# HD.net
KiCad netlist of a schematic drawn in EAGLE
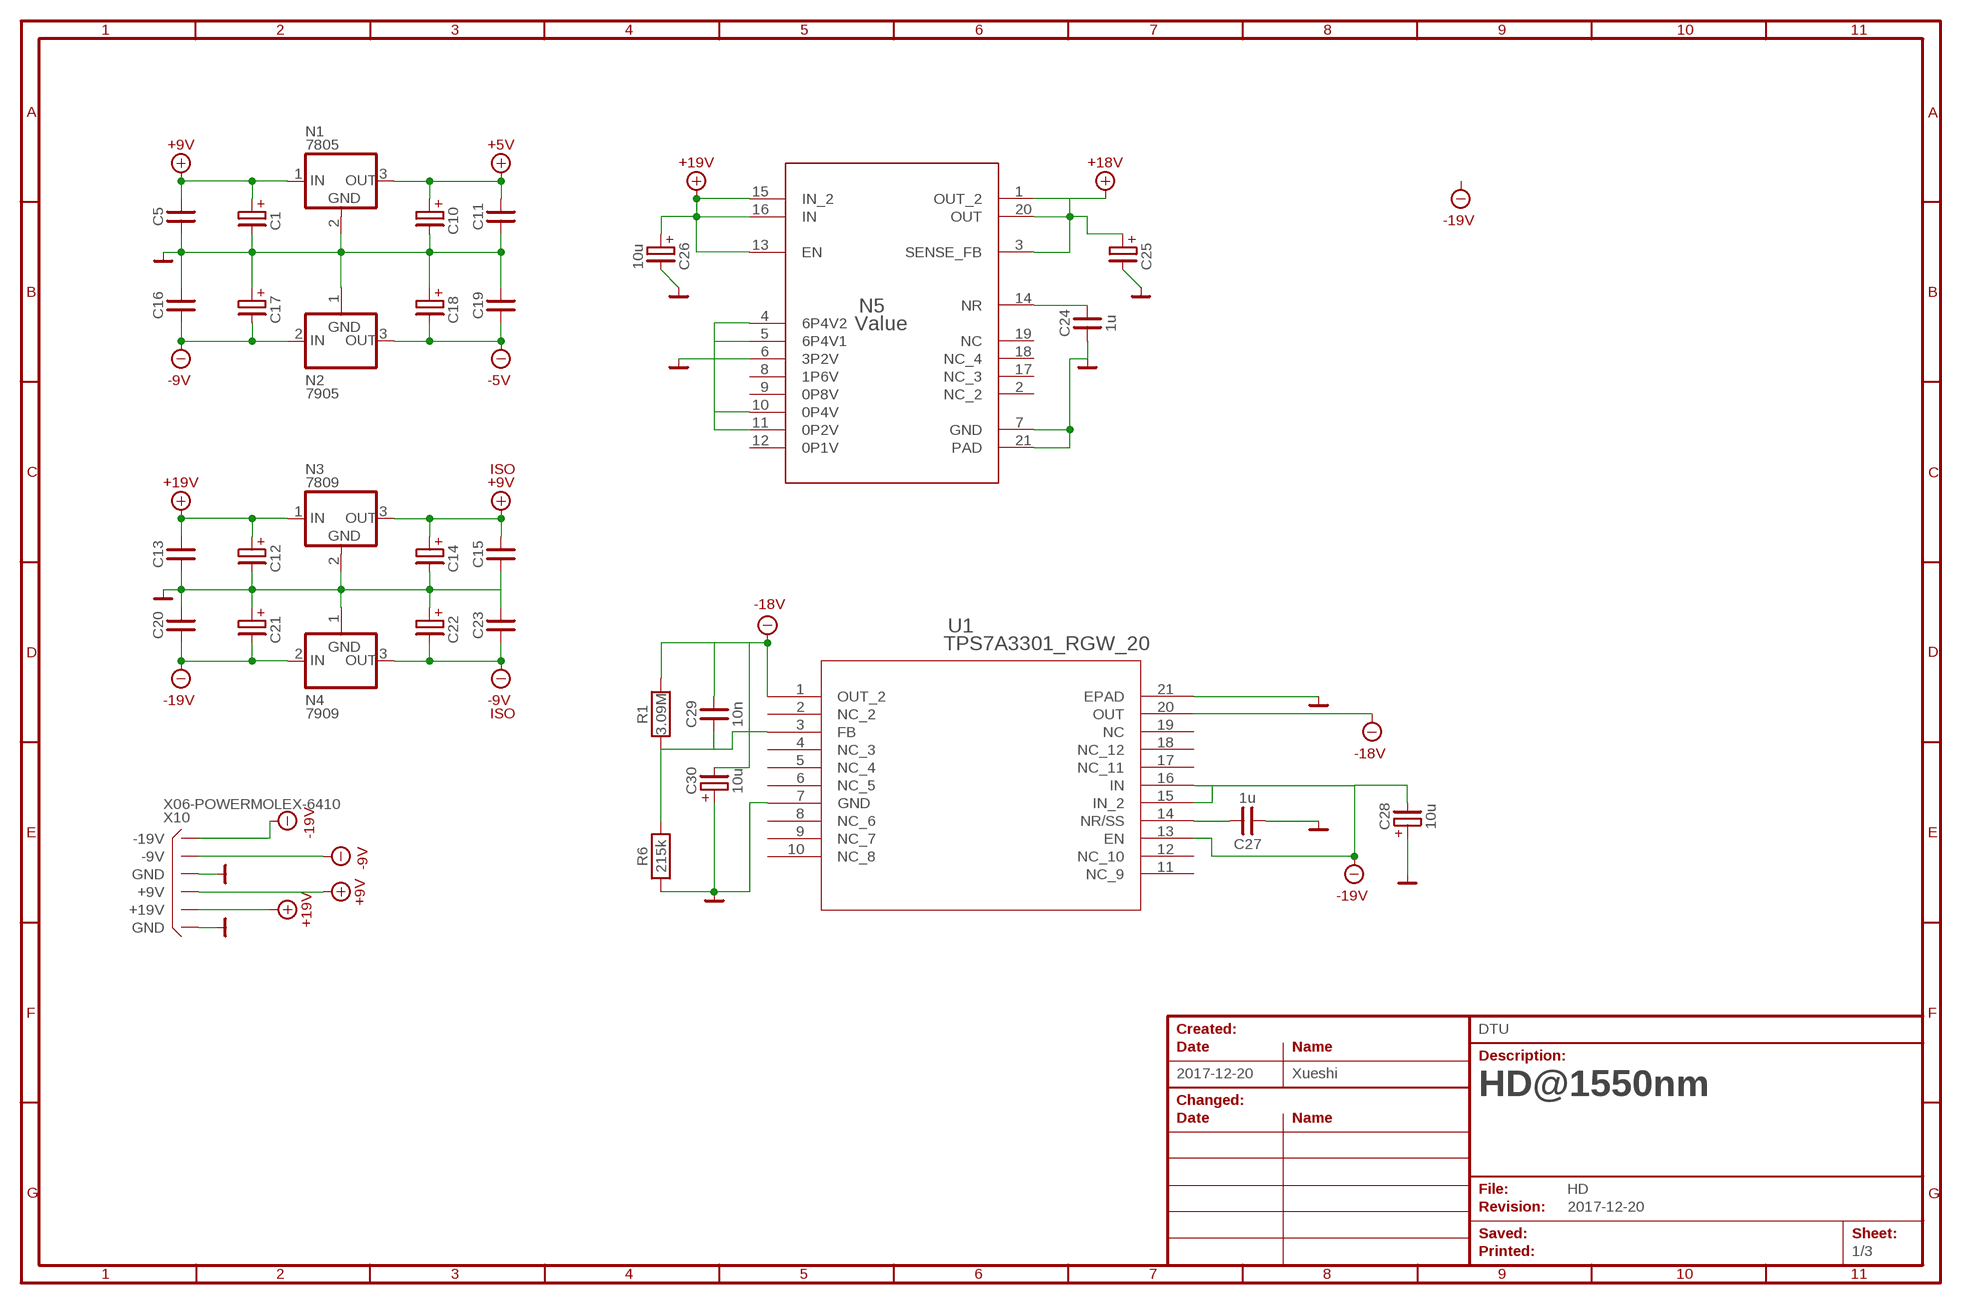
[diagram p0: schematic, sheet 1]
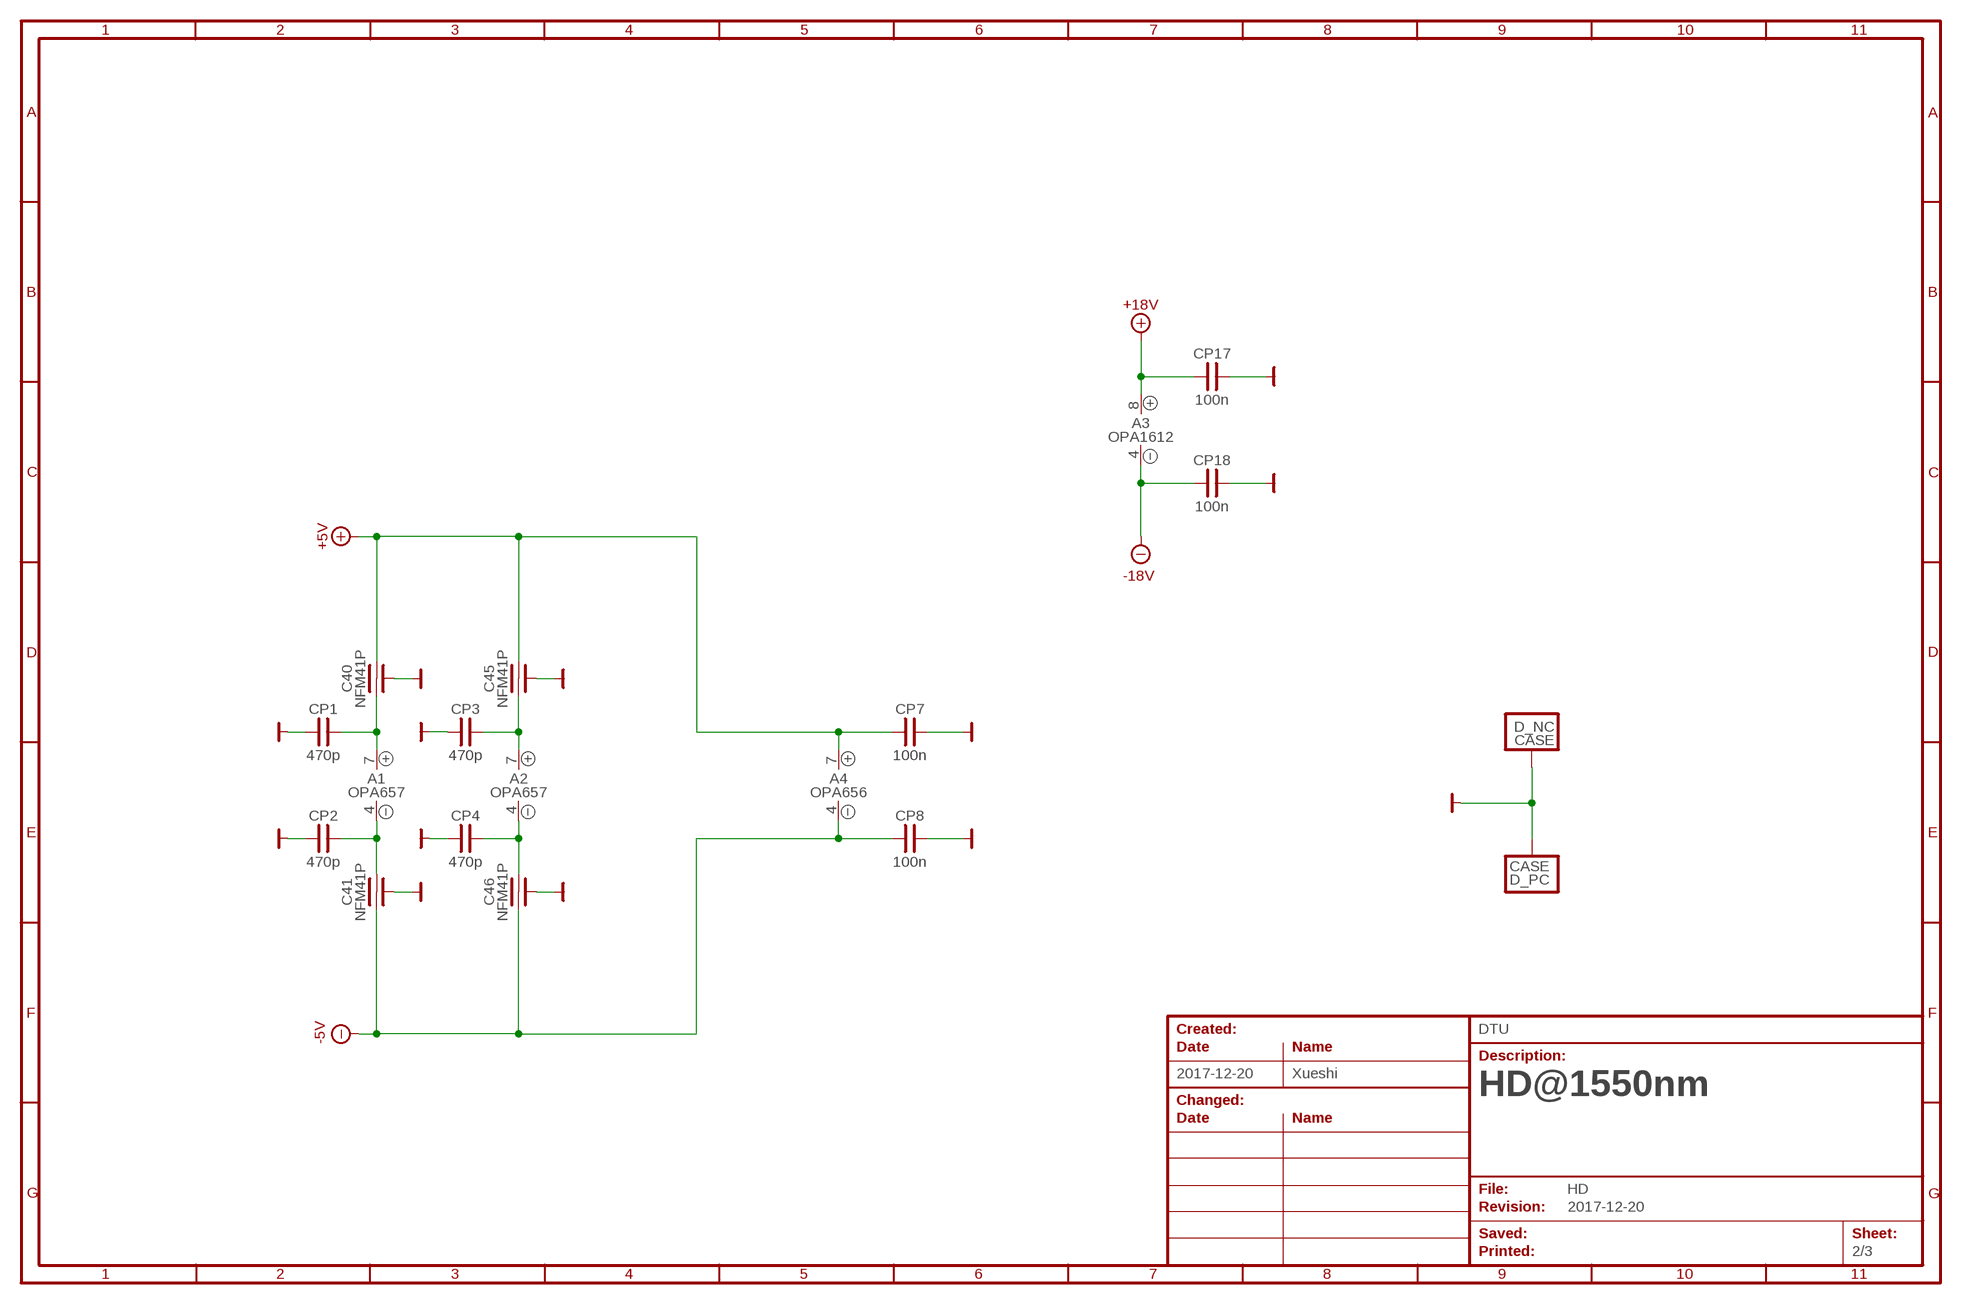
[diagram p1: schematic, sheet 2]
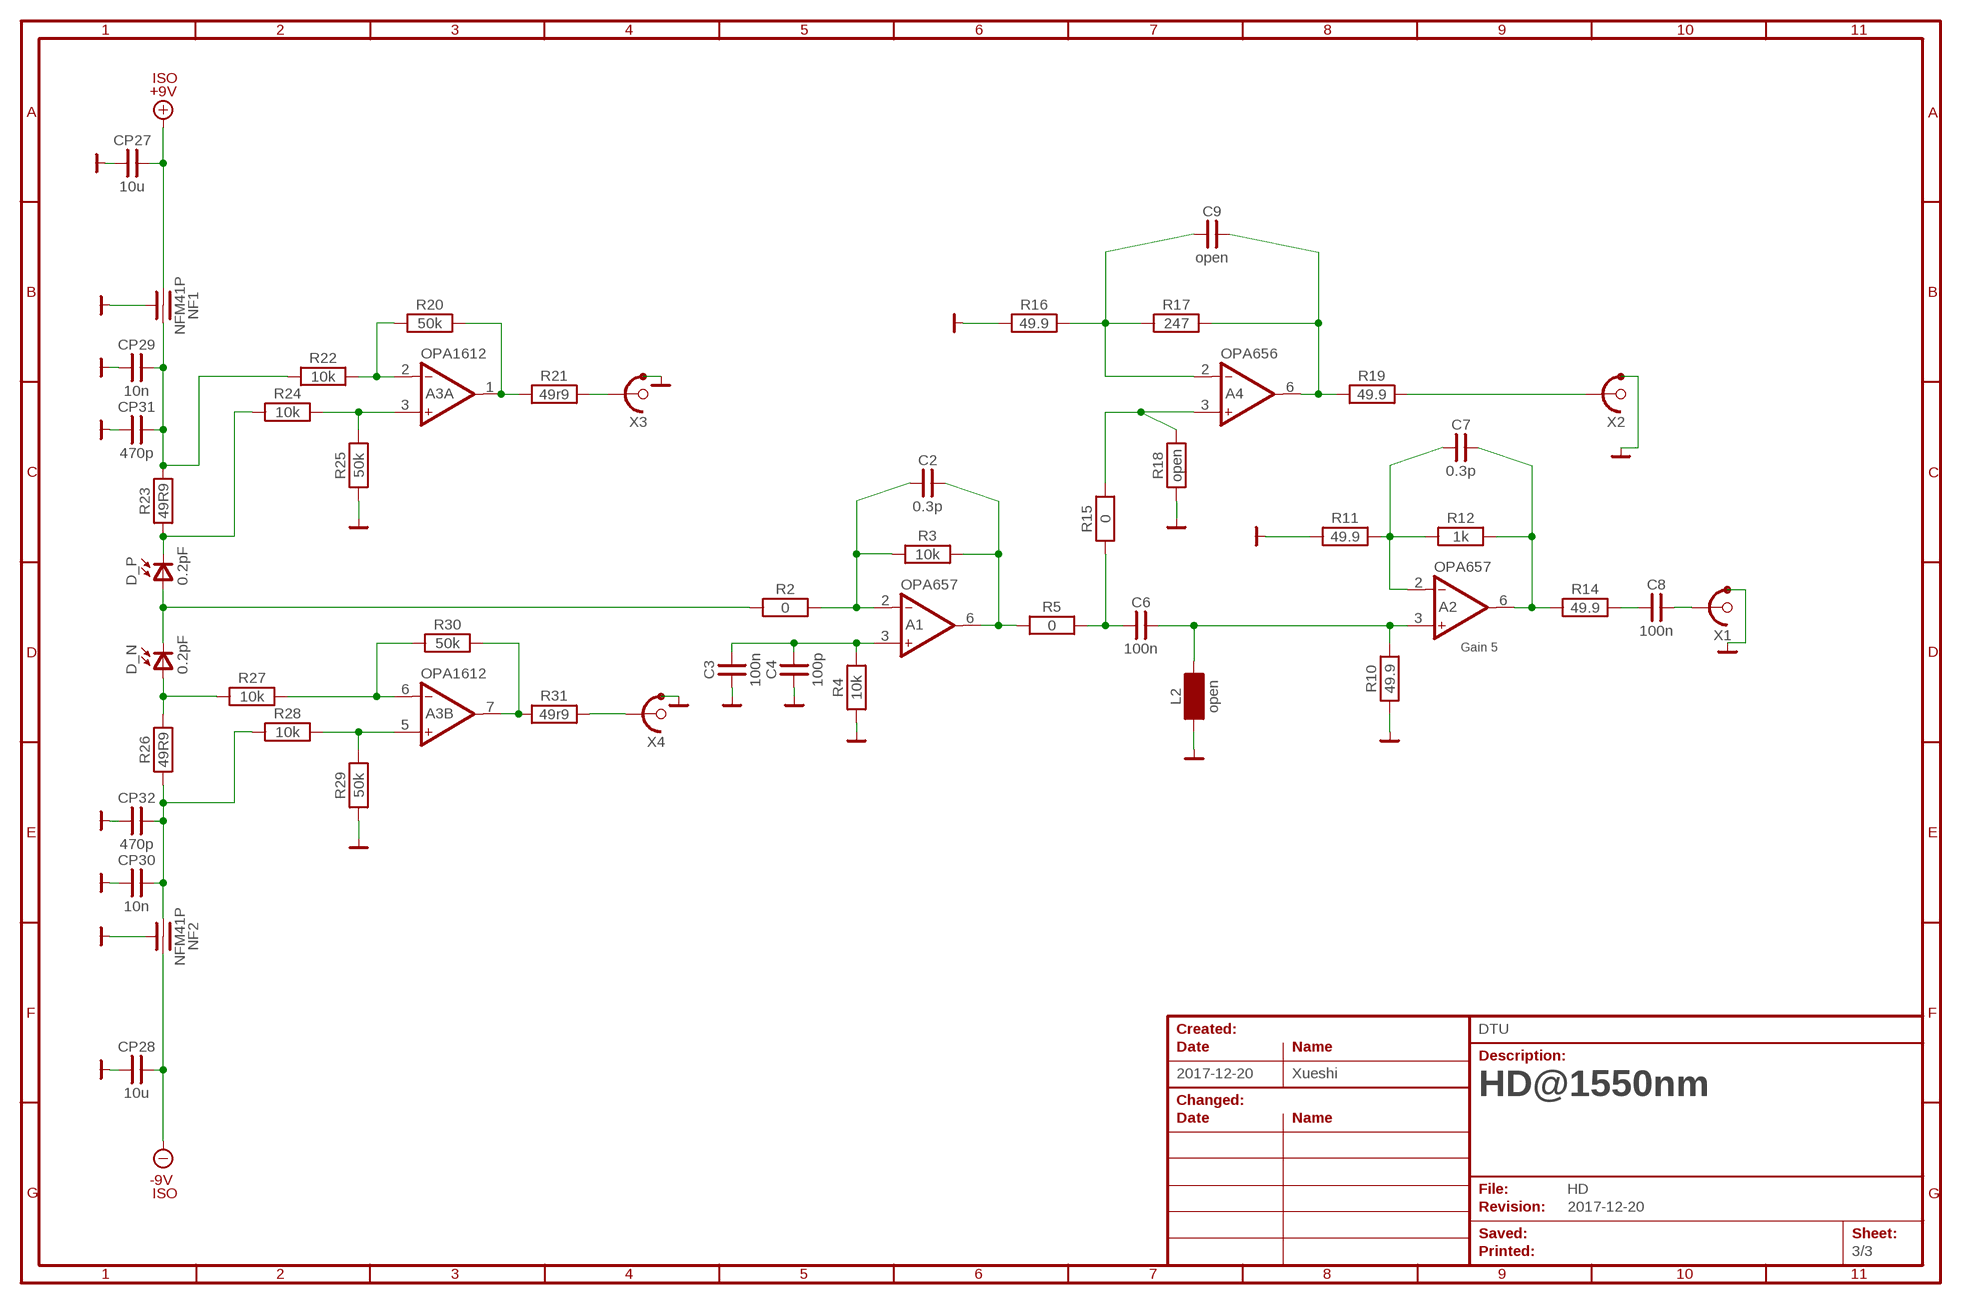
[diagram p2: schematic, sheet 3]

(export (version "E")
  (design (tool "Eeschema 10.0.6"))
  (components
    (comp (ref "A1")
      (value "OPA657")
      (footprint "eagle-import:SO08")
      (libsource (lib "eagle-import") (part "OPA657"))
    )
    (comp (ref "A2")
      (value "OPA657")
      (footprint "eagle-import:SO08")
      (libsource (lib "eagle-import") (part "OPA657"))
    )
    (comp (ref "A3")
      (value "OPA1612")
      (footprint "eagle-import:SO08")
      (libsource (lib "eagle-import") (part "OPA2107S"))
    )
    (comp (ref "A4")
      (value "OPA656")
      (footprint "eagle-import:SO08")
      (libsource (lib "eagle-import") (part "OPA657"))
    )
    (comp (ref "C2")
      (value "0.3p")
      (footprint "eagle-import:C0603")
      (libsource (lib "eagle-import") (part "C0603"))
    )
    (comp (ref "C3")
      (value "100n")
      (footprint "eagle-import:C0603")
      (libsource (lib "eagle-import") (part "C0603"))
    )
    (comp (ref "C4")
      (value "100p")
      (footprint "eagle-import:C0603")
      (libsource (lib "eagle-import") (part "C0603"))
    )
    (comp (ref "C6")
      (value "100n")
      (footprint "eagle-import:C0603")
      (libsource (lib "eagle-import") (part "C0603"))
    )
    (comp (ref "C7")
      (value "0.3p")
      (footprint "eagle-import:C0603")
      (libsource (lib "eagle-import") (part "C0603"))
    )
    (comp (ref "C8")
      (value "100n")
      (footprint "eagle-import:C0603")
      (libsource (lib "eagle-import") (part "C0603"))
    )
    (comp (ref "C9")
      (value "open")
      (footprint "eagle-import:C0603")
      (libsource (lib "eagle-import") (part "C0603"))
    )
    (comp (ref "CP27")
      (value "10u")
      (footprint "eagle-import:C1206")
      (libsource (lib "eagle-import") (part "C1206"))
    )
    (comp (ref "CP28")
      (value "10u")
      (footprint "eagle-import:C1206")
      (libsource (lib "eagle-import") (part "C1206"))
    )
    (comp (ref "CP29")
      (value "10n")
      (footprint "eagle-import:C0805")
      (libsource (lib "eagle-import") (part "C0805"))
    )
    (comp (ref "CP30")
      (value "10n")
      (footprint "eagle-import:C0805")
      (libsource (lib "eagle-import") (part "C0805"))
    )
    (comp (ref "CP31")
      (value "470p")
      (footprint "eagle-import:C0805")
      (libsource (lib "eagle-import") (part "C0805"))
    )
    (comp (ref "CP32")
      (value "470p")
      (footprint "eagle-import:C0805")
      (libsource (lib "eagle-import") (part "C0805"))
    )
    (comp (ref "D_N")
      (value "0.2pF")
      (footprint "eagle-import:STO5P")
      (libsource (lib "eagle-import") (part "DP-CLASER_COMPONENTS_PD"))
    )
    (comp (ref "D_P")
      (value "0.2pF")
      (footprint "eagle-import:STO5P")
      (libsource (lib "eagle-import") (part "DP-CLASER_COMPONENTS_PD"))
    )
    (comp (ref "L2")
      (value "open")
      (footprint "eagle-import:L0603")
      (libsource (lib "eagle-import") (part "L0603"))
    )
    (comp (ref "NF1")
      (value "NFM41P")
      (footprint "eagle-import:CF-NFM41P")
      (libsource (lib "eagle-import") (part "CF"))
    )
    (comp (ref "NF2")
      (value "NFM41P")
      (footprint "eagle-import:CF-NFM41P")
      (libsource (lib "eagle-import") (part "CF"))
    )
    (comp (ref "R2")
      (value "0")
      (footprint "eagle-import:R0603")
      (libsource (lib "eagle-import") (part "R0603"))
    )
    (comp (ref "R3")
      (value "10k")
      (footprint "eagle-import:R0603")
      (libsource (lib "eagle-import") (part "R0603"))
    )
    (comp (ref "R4")
      (value "10k")
      (footprint "eagle-import:R0603")
      (libsource (lib "eagle-import") (part "R0603"))
    )
    (comp (ref "R5")
      (value "0")
      (footprint "eagle-import:R0603")
      (libsource (lib "eagle-import") (part "R0603"))
    )
    (comp (ref "R10")
      (value "49.9")
      (footprint "eagle-import:R0603")
      (libsource (lib "eagle-import") (part "R0603"))
    )
    (comp (ref "R11")
      (value "49.9")
      (footprint "eagle-import:R0603")
      (libsource (lib "eagle-import") (part "R0603"))
    )
    (comp (ref "R12")
      (value "1k")
      (footprint "eagle-import:R0603")
      (libsource (lib "eagle-import") (part "R0603"))
    )
    (comp (ref "R14")
      (value "49.9")
      (footprint "eagle-import:R0603")
      (libsource (lib "eagle-import") (part "R0603"))
    )
    (comp (ref "R15")
      (value "0")
      (footprint "eagle-import:R0805")
      (libsource (lib "eagle-import") (part "R0805"))
    )
    (comp (ref "R16")
      (value "49.9")
      (footprint "eagle-import:R0603")
      (libsource (lib "eagle-import") (part "R0603"))
    )
    (comp (ref "R17")
      (value "247")
      (footprint "eagle-import:R0603")
      (libsource (lib "eagle-import") (part "R0603"))
    )
    (comp (ref "R18")
      (value "open")
      (footprint "eagle-import:R0603")
      (libsource (lib "eagle-import") (part "R0603"))
    )
    (comp (ref "R19")
      (value "49.9")
      (footprint "eagle-import:R0603")
      (libsource (lib "eagle-import") (part "R0603"))
    )
    (comp (ref "R20")
      (value "50k")
      (footprint "eagle-import:R0603")
      (libsource (lib "eagle-import") (part "R0603"))
    )
    (comp (ref "R21")
      (value "49r9")
      (footprint "eagle-import:R0603")
      (libsource (lib "eagle-import") (part "R0603"))
    )
    (comp (ref "R22")
      (value "10k")
      (footprint "eagle-import:R0603")
      (libsource (lib "eagle-import") (part "R0603"))
    )
    (comp (ref "R23")
      (value "49R9")
      (footprint "eagle-import:R0603")
      (libsource (lib "eagle-import") (part "R0603"))
    )
    (comp (ref "R24")
      (value "10k")
      (footprint "eagle-import:R0603")
      (libsource (lib "eagle-import") (part "R0603"))
    )
    (comp (ref "R25")
      (value "50k")
      (footprint "eagle-import:R0603")
      (libsource (lib "eagle-import") (part "R0603"))
    )
    (comp (ref "R26")
      (value "49R9")
      (footprint "eagle-import:R0603")
      (libsource (lib "eagle-import") (part "R0603"))
    )
    (comp (ref "R27")
      (value "10k")
      (footprint "eagle-import:R0603")
      (libsource (lib "eagle-import") (part "R0603"))
    )
    (comp (ref "R28")
      (value "10k")
      (footprint "eagle-import:R0603")
      (libsource (lib "eagle-import") (part "R0603"))
    )
    (comp (ref "R29")
      (value "50k")
      (footprint "eagle-import:R0603")
      (libsource (lib "eagle-import") (part "R0603"))
    )
    (comp (ref "R30")
      (value "50k")
      (footprint "eagle-import:R0603")
      (libsource (lib "eagle-import") (part "R0603"))
    )
    (comp (ref "R31")
      (value "49r9")
      (footprint "eagle-import:R0603")
      (libsource (lib "eagle-import") (part "R0603"))
    )
    (comp (ref "X1")
      (value "XS01-PCB")
      (footprint "eagle-import:XS01-UFL")
      (libsource (lib "eagle-import") (part "XS01-PCB"))
    )
    (comp (ref "X2")
      (value "XS01-PCB")
      (footprint "eagle-import:XS01-UFL")
      (libsource (lib "eagle-import") (part "XS01-PCB"))
    )
    (comp (ref "X3")
      (value "XS01-PCB")
      (footprint "eagle-import:XS01-UFL")
      (libsource (lib "eagle-import") (part "XS01-PCB"))
    )
    (comp (ref "X4")
      (value "XS01-PCB")
      (footprint "eagle-import:XS01-UFL")
      (libsource (lib "eagle-import") (part "XS01-PCB"))
    )
    (comp (ref "C40")
      (value "NFM41P")
      (footprint "eagle-import:CF-NFM41P")
      (libsource (lib "eagle-import") (part "CF"))
    )
    (comp (ref "C41")
      (value "NFM41P")
      (footprint "eagle-import:CF-NFM41P")
      (libsource (lib "eagle-import") (part "CF"))
    )
    (comp (ref "C45")
      (value "NFM41P")
      (footprint "eagle-import:CF-NFM41P")
      (libsource (lib "eagle-import") (part "CF"))
    )
    (comp (ref "C46")
      (value "NFM41P")
      (footprint "eagle-import:CF-NFM41P")
      (libsource (lib "eagle-import") (part "CF"))
    )
    (comp (ref "CP1")
      (value "470p")
      (footprint "eagle-import:C0603")
      (libsource (lib "eagle-import") (part "C0603"))
    )
    (comp (ref "CP2")
      (value "470p")
      (footprint "eagle-import:C0603")
      (libsource (lib "eagle-import") (part "C0603"))
    )
    (comp (ref "CP3")
      (value "470p")
      (footprint "eagle-import:C0603")
      (libsource (lib "eagle-import") (part "C0603"))
    )
    (comp (ref "CP4")
      (value "470p")
      (footprint "eagle-import:C0603")
      (libsource (lib "eagle-import") (part "C0603"))
    )
    (comp (ref "CP7")
      (value "100n")
      (footprint "eagle-import:C0603")
      (libsource (lib "eagle-import") (part "C0603"))
    )
    (comp (ref "CP8")
      (value "100n")
      (footprint "eagle-import:C0603")
      (libsource (lib "eagle-import") (part "C0603"))
    )
    (comp (ref "CP17")
      (value "100n")
      (footprint "eagle-import:C0603")
      (libsource (lib "eagle-import") (part "C0603"))
    )
    (comp (ref "CP18")
      (value "100n")
      (footprint "eagle-import:C0603")
      (libsource (lib "eagle-import") (part "C0603"))
    )
    (comp (ref "C1")
      (value "CEC")
      (footprint "eagle-import:CEC")
      (libsource (lib "eagle-import") (part "CEC"))
    )
    (comp (ref "C5")
      (value "C0805")
      (footprint "eagle-import:C0805")
      (libsource (lib "eagle-import") (part "C0805"))
    )
    (comp (ref "C10")
      (value "CEC")
      (footprint "eagle-import:CEC")
      (libsource (lib "eagle-import") (part "CEC"))
    )
    (comp (ref "C11")
      (value "C0805")
      (footprint "eagle-import:C0805")
      (libsource (lib "eagle-import") (part "C0805"))
    )
    (comp (ref "C12")
      (value "CEC")
      (footprint "eagle-import:CEC")
      (libsource (lib "eagle-import") (part "CEC"))
    )
    (comp (ref "C13")
      (value "C0805")
      (footprint "eagle-import:C0805")
      (libsource (lib "eagle-import") (part "C0805"))
    )
    (comp (ref "C14")
      (value "CEC")
      (footprint "eagle-import:CEC")
      (libsource (lib "eagle-import") (part "CEC"))
    )
    (comp (ref "C15")
      (value "C0805")
      (footprint "eagle-import:C0805")
      (libsource (lib "eagle-import") (part "C0805"))
    )
    (comp (ref "C16")
      (value "C0805")
      (footprint "eagle-import:C0805")
      (libsource (lib "eagle-import") (part "C0805"))
    )
    (comp (ref "C17")
      (value "CEC")
      (footprint "eagle-import:CEC")
      (libsource (lib "eagle-import") (part "CEC"))
    )
    (comp (ref "C18")
      (value "CEC")
      (footprint "eagle-import:CEC")
      (libsource (lib "eagle-import") (part "CEC"))
    )
    (comp (ref "C19")
      (value "C0805")
      (footprint "eagle-import:C0805")
      (libsource (lib "eagle-import") (part "C0805"))
    )
    (comp (ref "C20")
      (value "C0805")
      (footprint "eagle-import:C0805")
      (libsource (lib "eagle-import") (part "C0805"))
    )
    (comp (ref "C21")
      (value "CEC")
      (footprint "eagle-import:CEC")
      (libsource (lib "eagle-import") (part "CEC"))
    )
    (comp (ref "C22")
      (value "CEC")
      (footprint "eagle-import:CEC")
      (libsource (lib "eagle-import") (part "CEC"))
    )
    (comp (ref "C23")
      (value "C0805")
      (footprint "eagle-import:C0805")
      (libsource (lib "eagle-import") (part "C0805"))
    )
    (comp (ref "C24")
      (value "1u")
      (footprint "eagle-import:C0805")
      (libsource (lib "eagle-import") (part "C0805"))
    )
    (comp (ref "C25")
      (value "CEC")
      (footprint "eagle-import:CEC")
      (libsource (lib "eagle-import") (part "CEC"))
    )
    (comp (ref "C26")
      (value "10u")
      (footprint "eagle-import:CEC")
      (libsource (lib "eagle-import") (part "CEC"))
    )
    (comp (ref "C27")
      (value "1u")
      (footprint "eagle-import:C0805")
      (libsource (lib "eagle-import") (part "C0805"))
    )
    (comp (ref "C28")
      (value "10u")
      (footprint "eagle-import:CEC")
      (libsource (lib "eagle-import") (part "CEC"))
    )
    (comp (ref "C29")
      (value "10n")
      (footprint "eagle-import:C0805")
      (libsource (lib "eagle-import") (part "C0805"))
    )
    (comp (ref "C30")
      (value "10u")
      (footprint "eagle-import:CEC")
      (libsource (lib "eagle-import") (part "CEC"))
    )
    (comp (ref "N1")
      (value "7805")
      (footprint "eagle-import:TO252")
      (fields (field (name "TYPE") "7805"))
      (libsource (lib "eagle-import") (part "78S205"))
    )
    (comp (ref "N2")
      (value "7905")
      (footprint "eagle-import:TO252")
      (fields (field (name "TYPE") "7905"))
      (libsource (lib "eagle-import") (part "79S205"))
    )
    (comp (ref "N3")
      (value "7809")
      (footprint "eagle-import:TO252")
      (fields (field (name "TYPE") "7809"))
      (libsource (lib "eagle-import") (part "78S209"))
    )
    (comp (ref "N4")
      (value "7909")
      (footprint "eagle-import:TO252")
      (fields (field (name "TYPE") "7909"))
      (libsource (lib "eagle-import") (part "79S209"))
    )
    (comp (ref "N5")
      (value "Value")
      (footprint "eagle-import:RGW0020A")
      (fields (field (name "MANUFACTURER") "Texas Instruments") (field (name "PARTNUMBER") "TPS7A4701RGWR"))
      (libsource (lib "eagle-import") (part "TPS7A4701RGWR"))
    )
    (comp (ref "R1")
      (value "3.09M")
      (footprint "eagle-import:R0805")
      (libsource (lib "eagle-import") (part "R0805"))
    )
    (comp (ref "R6")
      (value "215k")
      (footprint "eagle-import:R0805")
      (libsource (lib "eagle-import") (part "R0805"))
    )
    (comp (ref "U1")
      (value "TPS7A3301_RGW_20")
      (footprint "eagle-import:RGW0020A")
      (fields
        (field (name "GENERIC_PART_NUMBER") "TPS7A3301")
        (field (name "MANUFACTURER") "Texas Instruments")
        (field (name "MANUFACTURER_PART_NUMBER") "tps7a3301_rgw_20")
      )
      (libsource (lib "eagle-import") (part "TPS7A3301_RGW_20"))
    )
    (comp (ref "X10")
      (value "X06-POWERMOLEX-6410")
      (footprint "eagle-import:X06-MOLEX-6410")
      (libsource (lib "eagle-import") (part "X06-POWERMOLEX-6410"))
    )
  )
  (nets
    (net (code "1") (name "+5V") (class "Default")
      (node (ref "A4") (pin "7") (pinfunction "V+_7") (pintype "power_in"))
      (node (ref "C10") (pin "+") (pinfunction "+_+") (pintype "passive"))
      (node (ref "C11") (pin "2") (pinfunction "2_2") (pintype "passive"))
      (node (ref "C40") (pin "2") (pinfunction "2_2") (pintype "passive"))
      (node (ref "C45") (pin "2") (pinfunction "2_2") (pintype "passive"))
      (node (ref "CP7") (pin "1") (pinfunction "1_1") (pintype "passive"))
      (node (ref "N1") (pin "3") (pinfunction "OUT_3") (pintype "power_in"))
    )
    (net (code "2") (name "+9V") (class "Default")
      (node (ref "C1") (pin "+") (pinfunction "+_+") (pintype "passive"))
      (node (ref "C5") (pin "1") (pinfunction "1_1") (pintype "passive"))
      (node (ref "N1") (pin "1") (pinfunction "IN_1") (pintype "power_in"))
      (node (ref "X10") (pin "P$4") (pinfunction "+9V_P$4") (pintype "bidirectional"))
    )
    (net (code "3") (name "+9VISO") (class "Default")
      (node (ref "C14") (pin "+") (pinfunction "+_+") (pintype "passive"))
      (node (ref "C15") (pin "2") (pinfunction "2_2") (pintype "passive"))
      (node (ref "CP27") (pin "2") (pinfunction "2_2") (pintype "passive"))
      (node (ref "N3") (pin "3") (pinfunction "OUT_3") (pintype "power_in"))
      (node (ref "NF1") (pin "1") (pinfunction "1_1") (pintype "passive"))
    )
    (net (code "4") (name "+18V") (class "Default")
      (node (ref "A3") (pin "8") (pinfunction "V+_8") (pintype "power_in"))
      (node (ref "C25") (pin "+") (pinfunction "+_+") (pintype "passive"))
      (node (ref "CP17") (pin "1") (pinfunction "1_1") (pintype "passive"))
      (node (ref "N5") (pin "1") (pinfunction "OUT_2_1") (pintype "power_in"))
      (node (ref "N5") (pin "20") (pinfunction "OUT_20") (pintype "power_in"))
      (node (ref "N5") (pin "3") (pinfunction "SENSE_FB_3") (pintype "input"))
    )
    (net (code "5") (name "+19V") (class "Default")
      (node (ref "C12") (pin "+") (pinfunction "+_+") (pintype "passive"))
      (node (ref "C13") (pin "1") (pinfunction "1_1") (pintype "passive"))
      (node (ref "C26") (pin "+") (pinfunction "+_+") (pintype "passive"))
      (node (ref "N3") (pin "1") (pinfunction "IN_1") (pintype "power_in"))
      (node (ref "N5") (pin "13") (pinfunction "EN_13") (pintype "input"))
      (node (ref "N5") (pin "15") (pinfunction "IN_2_15") (pintype "power_in"))
      (node (ref "N5") (pin "16") (pinfunction "IN_16") (pintype "power_in"))
      (node (ref "X10") (pin "P$5") (pinfunction "+19V_P$5") (pintype "bidirectional"))
    )
    (net (code "6") (name "-5V") (class "Default")
      (node (ref "A4") (pin "4") (pinfunction "V-_4") (pintype "power_in"))
      (node (ref "C18") (pin "-") (pinfunction "-_-") (pintype "passive"))
      (node (ref "C19") (pin "1") (pinfunction "1_1") (pintype "passive"))
      (node (ref "C41") (pin "1") (pinfunction "1_1") (pintype "passive"))
      (node (ref "C46") (pin "1") (pinfunction "1_1") (pintype "passive"))
      (node (ref "CP8") (pin "1") (pinfunction "1_1") (pintype "passive"))
      (node (ref "N2") (pin "3") (pinfunction "OUT_3") (pintype "power_in"))
    )
    (net (code "7") (name "-9V") (class "Default")
      (node (ref "C16") (pin "2") (pinfunction "2_2") (pintype "passive"))
      (node (ref "C17") (pin "-") (pinfunction "-_-") (pintype "passive"))
      (node (ref "N2") (pin "2") (pinfunction "IN_2") (pintype "power_in"))
      (node (ref "X10") (pin "P$2") (pinfunction "-9V_P$2") (pintype "bidirectional"))
    )
    (net (code "8") (name "-9VISO") (class "Default")
      (node (ref "C22") (pin "-") (pinfunction "-_-") (pintype "passive"))
      (node (ref "C23") (pin "1") (pinfunction "1_1") (pintype "passive"))
      (node (ref "CP28") (pin "2") (pinfunction "2_2") (pintype "passive"))
      (node (ref "N4") (pin "3") (pinfunction "OUT_3") (pintype "power_in"))
      (node (ref "NF2") (pin "2") (pinfunction "2_2") (pintype "passive"))
    )
    (net (code "9") (name "-18V") (class "Default")
      (node (ref "A3") (pin "4") (pinfunction "V-_4") (pintype "power_in"))
      (node (ref "C29") (pin "2") (pinfunction "2_2") (pintype "passive"))
      (node (ref "C30") (pin "-") (pinfunction "-_-") (pintype "passive"))
      (node (ref "CP18") (pin "1") (pinfunction "1_1") (pintype "passive"))
      (node (ref "R1") (pin "2") (pinfunction "2_2") (pintype "passive"))
      (node (ref "U1") (pin "1") (pinfunction "OUT_2_1") (pintype "output"))
      (node (ref "U1") (pin "20") (pinfunction "OUT_20") (pintype "output"))
    )
    (net (code "10") (name "-19V") (class "Default")
      (node (ref "C20") (pin "2") (pinfunction "2_2") (pintype "passive"))
      (node (ref "C21") (pin "-") (pinfunction "-_-") (pintype "passive"))
      (node (ref "C28") (pin "-") (pinfunction "-_-") (pintype "passive"))
      (node (ref "N4") (pin "2") (pinfunction "IN_2") (pintype "power_in"))
      (node (ref "U1") (pin "13") (pinfunction "EN_13") (pintype "passive"))
      (node (ref "U1") (pin "15") (pinfunction "IN_2_15") (pintype "input"))
      (node (ref "U1") (pin "16") (pinfunction "IN_16") (pintype "input"))
      (node (ref "X10") (pin "P$1") (pinfunction "-19V_P$1") (pintype "bidirectional"))
    )
    (net (code "11") (name "GND") (class "Default")
      (node (ref "C1") (pin "-") (pinfunction "-_-") (pintype "passive"))
      (node (ref "C10") (pin "-") (pinfunction "-_-") (pintype "passive"))
      (node (ref "C11") (pin "1") (pinfunction "1_1") (pintype "passive"))
      (node (ref "C12") (pin "-") (pinfunction "-_-") (pintype "passive"))
      (node (ref "C13") (pin "2") (pinfunction "2_2") (pintype "passive"))
      (node (ref "C14") (pin "-") (pinfunction "-_-") (pintype "passive"))
      (node (ref "C15") (pin "1") (pinfunction "1_1") (pintype "passive"))
      (node (ref "C16") (pin "1") (pinfunction "1_1") (pintype "passive"))
      (node (ref "C17") (pin "+") (pinfunction "+_+") (pintype "passive"))
      (node (ref "C18") (pin "+") (pinfunction "+_+") (pintype "passive"))
      (node (ref "C19") (pin "2") (pinfunction "2_2") (pintype "passive"))
      (node (ref "C20") (pin "1") (pinfunction "1_1") (pintype "passive"))
      (node (ref "C21") (pin "+") (pinfunction "+_+") (pintype "passive"))
      (node (ref "C22") (pin "+") (pinfunction "+_+") (pintype "passive"))
      (node (ref "C23") (pin "2") (pinfunction "2_2") (pintype "passive"))
      (node (ref "C24") (pin "1") (pinfunction "1_1") (pintype "passive"))
      (node (ref "C25") (pin "-") (pinfunction "-_-") (pintype "passive"))
      (node (ref "C26") (pin "-") (pinfunction "-_-") (pintype "passive"))
      (node (ref "C27") (pin "1") (pinfunction "1_1") (pintype "passive"))
      (node (ref "C28") (pin "+") (pinfunction "+_+") (pintype "passive"))
      (node (ref "C3") (pin "1") (pinfunction "1_1") (pintype "passive"))
      (node (ref "C30") (pin "+") (pinfunction "+_+") (pintype "passive"))
      (node (ref "C4") (pin "1") (pinfunction "1_1") (pintype "passive"))
      (node (ref "C40") (pin "GND") (pinfunction "GND_GND") (pintype "passive"))
      (node (ref "C41") (pin "GND") (pinfunction "GND_GND") (pintype "passive"))
      (node (ref "C45") (pin "GND") (pinfunction "GND_GND") (pintype "passive"))
      (node (ref "C46") (pin "GND") (pinfunction "GND_GND") (pintype "passive"))
      (node (ref "C5") (pin "2") (pinfunction "2_2") (pintype "passive"))
      (node (ref "CP1") (pin "1") (pinfunction "1_1") (pintype "passive"))
      (node (ref "CP17") (pin "2") (pinfunction "2_2") (pintype "passive"))
      (node (ref "CP18") (pin "2") (pinfunction "2_2") (pintype "passive"))
      (node (ref "CP2") (pin "1") (pinfunction "1_1") (pintype "passive"))
      (node (ref "CP27") (pin "1") (pinfunction "1_1") (pintype "passive"))
      (node (ref "CP28") (pin "1") (pinfunction "1_1") (pintype "passive"))
      (node (ref "CP29") (pin "1") (pinfunction "1_1") (pintype "passive"))
      (node (ref "CP3") (pin "1") (pinfunction "1_1") (pintype "passive"))
      (node (ref "CP30") (pin "1") (pinfunction "1_1") (pintype "passive"))
      (node (ref "CP31") (pin "1") (pinfunction "1_1") (pintype "passive"))
      (node (ref "CP32") (pin "1") (pinfunction "1_1") (pintype "passive"))
      (node (ref "CP4") (pin "1") (pinfunction "1_1") (pintype "passive"))
      (node (ref "CP7") (pin "2") (pinfunction "2_2") (pintype "passive"))
      (node (ref "CP8") (pin "2") (pinfunction "2_2") (pintype "passive"))
      (node (ref "D_N") (pin "3") (pinfunction "CASE_3") (pintype "bidirectional"))
      (node (ref "D_P") (pin "3") (pinfunction "CASE_3") (pintype "bidirectional"))
      (node (ref "L2") (pin "1") (pinfunction "1_1") (pintype "passive"))
      (node (ref "N1") (pin "2") (pinfunction "GND_2") (pintype "power_in"))
      (node (ref "N2") (pin "1") (pinfunction "GND_1") (pintype "power_in"))
      (node (ref "N3") (pin "2") (pinfunction "GND_2") (pintype "power_in"))
      (node (ref "N4") (pin "1") (pinfunction "GND_1") (pintype "power_in"))
      (node (ref "N5") (pin "10") (pinfunction "0P4V_10") (pintype "passive"))
      (node (ref "N5") (pin "11") (pinfunction "0P2V_11") (pintype "passive"))
      (node (ref "N5") (pin "21") (pinfunction "PAD_21") (pintype "passive"))
      (node (ref "N5") (pin "4") (pinfunction "6P4V2_4") (pintype "passive"))
      (node (ref "N5") (pin "5") (pinfunction "6P4V1_5") (pintype "passive"))
      (node (ref "N5") (pin "6") (pinfunction "3P2V_6") (pintype "passive"))
      (node (ref "N5") (pin "7") (pinfunction "GND_7") (pintype "power_in"))
      (node (ref "NF1") (pin "GND") (pinfunction "GND_GND") (pintype "passive"))
      (node (ref "NF2") (pin "GND") (pinfunction "GND_GND") (pintype "passive"))
      (node (ref "R10") (pin "1") (pinfunction "1_1") (pintype "passive"))
      (node (ref "R11") (pin "1") (pinfunction "1_1") (pintype "passive"))
      (node (ref "R16") (pin "1") (pinfunction "1_1") (pintype "passive"))
      (node (ref "R18") (pin "1") (pinfunction "1_1") (pintype "passive"))
      (node (ref "R25") (pin "1") (pinfunction "1_1") (pintype "passive"))
      (node (ref "R29") (pin "1") (pinfunction "1_1") (pintype "passive"))
      (node (ref "R4") (pin "1") (pinfunction "1_1") (pintype "passive"))
      (node (ref "R6") (pin "1") (pinfunction "1_1") (pintype "passive"))
      (node (ref "U1") (pin "21") (pinfunction "EPAD_21") (pintype "passive"))
      (node (ref "U1") (pin "7") (pinfunction "GND_7") (pintype "power_in"))
      (node (ref "X1") (pin "GND1") (pinfunction "GND_GND1") (pintype "bidirectional"))
      (node (ref "X1") (pin "GND2") (pinfunction "GND_GND2") (pintype "bidirectional"))
      (node (ref "X10") (pin "P$3") (pinfunction "GND_P$3") (pintype "bidirectional"))
      (node (ref "X10") (pin "P$6") (pinfunction "GND_P$6") (pintype "bidirectional"))
      (node (ref "X2") (pin "GND1") (pinfunction "GND_GND1") (pintype "bidirectional"))
      (node (ref "X2") (pin "GND2") (pinfunction "GND_GND2") (pintype "bidirectional"))
      (node (ref "X3") (pin "GND1") (pinfunction "GND_GND1") (pintype "bidirectional"))
      (node (ref "X3") (pin "GND2") (pinfunction "GND_GND2") (pintype "bidirectional"))
      (node (ref "X4") (pin "GND1") (pinfunction "GND_GND1") (pintype "bidirectional"))
      (node (ref "X4") (pin "GND2") (pinfunction "GND_GND2") (pintype "bidirectional"))
    )
    (net (code "12") (name "Net-(A1A-IN+)") (class "Default")
      (node (ref "A1") (pin "3") (pinfunction "IN+_3") (pintype "input"))
      (node (ref "C3") (pin "2") (pinfunction "2_2") (pintype "passive"))
      (node (ref "C4") (pin "2") (pinfunction "2_2") (pintype "passive"))
      (node (ref "R4") (pin "2") (pinfunction "2_2") (pintype "passive"))
    )
    (net (code "13") (name "Net-(A1A-IN-)") (class "Default")
      (node (ref "A1") (pin "2") (pinfunction "IN-_2") (pintype "input"))
      (node (ref "C2") (pin "1") (pinfunction "1_1") (pintype "passive"))
      (node (ref "R2") (pin "2") (pinfunction "2_2") (pintype "passive"))
      (node (ref "R3") (pin "1") (pinfunction "1_1") (pintype "passive"))
    )
    (net (code "14") (name "Net-(A1A-OUT)") (class "Default")
      (node (ref "A1") (pin "6") (pinfunction "OUT_6") (pintype "output"))
      (node (ref "C2") (pin "2") (pinfunction "2_2") (pintype "passive"))
      (node (ref "R3") (pin "2") (pinfunction "2_2") (pintype "passive"))
      (node (ref "R5") (pin "1") (pinfunction "1_1") (pintype "passive"))
    )
    (net (code "15") (name "Net-(A1B-V+)") (class "Default")
      (node (ref "A1") (pin "7") (pinfunction "V+_7") (pintype "power_in"))
      (node (ref "C40") (pin "1") (pinfunction "1_1") (pintype "passive"))
      (node (ref "CP1") (pin "2") (pinfunction "2_2") (pintype "passive"))
    )
    (net (code "16") (name "Net-(A1B-V-)") (class "Default")
      (node (ref "A1") (pin "4") (pinfunction "V-_4") (pintype "power_in"))
      (node (ref "C41") (pin "2") (pinfunction "2_2") (pintype "passive"))
      (node (ref "CP2") (pin "2") (pinfunction "2_2") (pintype "passive"))
    )
    (net (code "17") (name "Net-(A2A-IN+)") (class "Default")
      (node (ref "A2") (pin "3") (pinfunction "IN+_3") (pintype "input"))
      (node (ref "C6") (pin "2") (pinfunction "2_2") (pintype "passive"))
      (node (ref "L2") (pin "2") (pinfunction "2_2") (pintype "passive"))
      (node (ref "R10") (pin "2") (pinfunction "2_2") (pintype "passive"))
    )
    (net (code "18") (name "Net-(A2A-IN-)") (class "Default")
      (node (ref "A2") (pin "2") (pinfunction "IN-_2") (pintype "input"))
      (node (ref "C7") (pin "1") (pinfunction "1_1") (pintype "passive"))
      (node (ref "R11") (pin "2") (pinfunction "2_2") (pintype "passive"))
      (node (ref "R12") (pin "1") (pinfunction "1_1") (pintype "passive"))
    )
    (net (code "19") (name "Net-(A2A-OUT)") (class "Default")
      (node (ref "A2") (pin "6") (pinfunction "OUT_6") (pintype "output"))
      (node (ref "C7") (pin "2") (pinfunction "2_2") (pintype "passive"))
      (node (ref "R12") (pin "2") (pinfunction "2_2") (pintype "passive"))
      (node (ref "R14") (pin "1") (pinfunction "1_1") (pintype "passive"))
    )
    (net (code "20") (name "Net-(A2B-V+)") (class "Default")
      (node (ref "A2") (pin "7") (pinfunction "V+_7") (pintype "power_in"))
      (node (ref "C45") (pin "1") (pinfunction "1_1") (pintype "passive"))
      (node (ref "CP3") (pin "2") (pinfunction "2_2") (pintype "passive"))
    )
    (net (code "21") (name "Net-(A2B-V-)") (class "Default")
      (node (ref "A2") (pin "4") (pinfunction "V-_4") (pintype "power_in"))
      (node (ref "C46") (pin "2") (pinfunction "2_2") (pintype "passive"))
      (node (ref "CP4") (pin "2") (pinfunction "2_2") (pintype "passive"))
    )
    (net (code "22") (name "Net-(A3A-IN+)") (class "Default")
      (node (ref "A3") (pin "3") (pinfunction "IN+_3") (pintype "input"))
      (node (ref "R24") (pin "2") (pinfunction "2_2") (pintype "passive"))
      (node (ref "R25") (pin "2") (pinfunction "2_2") (pintype "passive"))
    )
    (net (code "23") (name "Net-(A3A-IN-)") (class "Default")
      (node (ref "A3") (pin "2") (pinfunction "IN-_2") (pintype "input"))
      (node (ref "R20") (pin "1") (pinfunction "1_1") (pintype "passive"))
      (node (ref "R22") (pin "2") (pinfunction "2_2") (pintype "passive"))
    )
    (net (code "24") (name "Net-(A3A-OUT)") (class "Default")
      (node (ref "A3") (pin "1") (pinfunction "OUT_1") (pintype "output"))
      (node (ref "R20") (pin "2") (pinfunction "2_2") (pintype "passive"))
      (node (ref "R21") (pin "1") (pinfunction "1_1") (pintype "passive"))
    )
    (net (code "25") (name "Net-(A3B-IN+)") (class "Default")
      (node (ref "A3") (pin "5") (pinfunction "IN+_5") (pintype "input"))
      (node (ref "R28") (pin "2") (pinfunction "2_2") (pintype "passive"))
      (node (ref "R29") (pin "2") (pinfunction "2_2") (pintype "passive"))
    )
    (net (code "26") (name "Net-(A3B-IN-)") (class "Default")
      (node (ref "A3") (pin "6") (pinfunction "IN-_6") (pintype "input"))
      (node (ref "R27") (pin "2") (pinfunction "2_2") (pintype "passive"))
      (node (ref "R30") (pin "1") (pinfunction "1_1") (pintype "passive"))
    )
    (net (code "27") (name "Net-(A3B-OUT)") (class "Default")
      (node (ref "A3") (pin "7") (pinfunction "OUT_7") (pintype "output"))
      (node (ref "R30") (pin "2") (pinfunction "2_2") (pintype "passive"))
      (node (ref "R31") (pin "1") (pinfunction "1_1") (pintype "passive"))
    )
    (net (code "28") (name "Net-(A4A-IN+)") (class "Default")
      (node (ref "A4") (pin "3") (pinfunction "IN+_3") (pintype "input"))
      (node (ref "R15") (pin "2") (pinfunction "2_2") (pintype "passive"))
      (node (ref "R18") (pin "2") (pinfunction "2_2") (pintype "passive"))
    )
    (net (code "29") (name "Net-(A4A-IN-)") (class "Default")
      (node (ref "A4") (pin "2") (pinfunction "IN-_2") (pintype "input"))
      (node (ref "C9") (pin "1") (pinfunction "1_1") (pintype "passive"))
      (node (ref "R16") (pin "2") (pinfunction "2_2") (pintype "passive"))
      (node (ref "R17") (pin "1") (pinfunction "1_1") (pintype "passive"))
    )
    (net (code "30") (name "Net-(A4A-OUT)") (class "Default")
      (node (ref "A4") (pin "6") (pinfunction "OUT_6") (pintype "output"))
      (node (ref "C9") (pin "2") (pinfunction "2_2") (pintype "passive"))
      (node (ref "R17") (pin "2") (pinfunction "2_2") (pintype "passive"))
      (node (ref "R19") (pin "1") (pinfunction "1_1") (pintype "passive"))
    )
    (net (code "31") (name "Net-(C6-Pad1)") (class "Default")
      (node (ref "C6") (pin "1") (pinfunction "1_1") (pintype "passive"))
      (node (ref "R15") (pin "1") (pinfunction "1_1") (pintype "passive"))
      (node (ref "R5") (pin "2") (pinfunction "2_2") (pintype "passive"))
    )
    (net (code "32") (name "Net-(C8-Pad1)") (class "Default")
      (node (ref "C8") (pin "1") (pinfunction "1_1") (pintype "passive"))
      (node (ref "R14") (pin "2") (pinfunction "2_2") (pintype "passive"))
    )
    (net (code "33") (name "Net-(C8-Pad2)") (class "Default")
      (node (ref "C8") (pin "2") (pinfunction "2_2") (pintype "passive"))
      (node (ref "X1") (pin "SIG") (pinfunction "SIG_SIG") (pintype "bidirectional"))
    )
    (net (code "34") (name "Net-(CP29-Pad2)") (class "Default")
      (node (ref "CP29") (pin "2") (pinfunction "2_2") (pintype "passive"))
      (node (ref "CP31") (pin "2") (pinfunction "2_2") (pintype "passive"))
      (node (ref "NF1") (pin "2") (pinfunction "2_2") (pintype "passive"))
      (node (ref "R22") (pin "1") (pinfunction "1_1") (pintype "passive"))
      (node (ref "R23") (pin "2") (pinfunction "2_2") (pintype "passive"))
    )
    (net (code "35") (name "Net-(CP30-Pad2)") (class "Default")
      (node (ref "CP30") (pin "2") (pinfunction "2_2") (pintype "passive"))
      (node (ref "CP32") (pin "2") (pinfunction "2_2") (pintype "passive"))
      (node (ref "NF2") (pin "1") (pinfunction "1_1") (pintype "passive"))
      (node (ref "R26") (pin "1") (pinfunction "1_1") (pintype "passive"))
      (node (ref "R28") (pin "1") (pinfunction "1_1") (pintype "passive"))
    )
    (net (code "36") (name "Net-(D_NA-A)") (class "Default")
      (node (ref "D_N") (pin "1") (pinfunction "A_1") (pintype "passive"))
      (node (ref "R26") (pin "2") (pinfunction "2_2") (pintype "passive"))
      (node (ref "R27") (pin "1") (pinfunction "1_1") (pintype "passive"))
    )
    (net (code "37") (name "Net-(D_NA-C)") (class "Default")
      (node (ref "D_N") (pin "2") (pinfunction "C_2") (pintype "passive"))
      (node (ref "D_P") (pin "1") (pinfunction "A_1") (pintype "passive"))
      (node (ref "R2") (pin "1") (pinfunction "1_1") (pintype "passive"))
    )
    (net (code "38") (name "Net-(D_PA-C)") (class "Default")
      (node (ref "D_P") (pin "2") (pinfunction "C_2") (pintype "passive"))
      (node (ref "R23") (pin "1") (pinfunction "1_1") (pintype "passive"))
      (node (ref "R24") (pin "1") (pinfunction "1_1") (pintype "passive"))
    )
    (net (code "39") (name "Net-(N5-NR)") (class "Default")
      (node (ref "C24") (pin "2") (pinfunction "2_2") (pintype "passive"))
      (node (ref "N5") (pin "14") (pinfunction "NR_14") (pintype "input"))
    )
    (net (code "40") (name "Net-(R19-Pad2)") (class "Default")
      (node (ref "R19") (pin "2") (pinfunction "2_2") (pintype "passive"))
      (node (ref "X2") (pin "SIG") (pinfunction "SIG_SIG") (pintype "bidirectional"))
    )
    (net (code "41") (name "Net-(R21-Pad2)") (class "Default")
      (node (ref "R21") (pin "2") (pinfunction "2_2") (pintype "passive"))
      (node (ref "X3") (pin "SIG") (pinfunction "SIG_SIG") (pintype "bidirectional"))
    )
    (net (code "42") (name "Net-(R31-Pad2)") (class "Default")
      (node (ref "R31") (pin "2") (pinfunction "2_2") (pintype "passive"))
      (node (ref "X4") (pin "SIG") (pinfunction "SIG_SIG") (pintype "bidirectional"))
    )
    (net (code "43") (name "Net-(U1-FB)") (class "Default")
      (node (ref "C29") (pin "1") (pinfunction "1_1") (pintype "passive"))
      (node (ref "R1") (pin "1") (pinfunction "1_1") (pintype "passive"))
      (node (ref "R6") (pin "2") (pinfunction "2_2") (pintype "passive"))
      (node (ref "U1") (pin "3") (pinfunction "FB_3") (pintype "passive"))
    )
    (net (code "44") (name "Net-(U1-NR{slash}SS)") (class "Default")
      (node (ref "C27") (pin "2") (pinfunction "2_2") (pintype "passive"))
      (node (ref "U1") (pin "14") (pinfunction "NR/SS_14") (pintype "passive"))
    )
    (net (code "45") (name "unconnected-(N5-0P1V-Pad12)") (class "Default")
      (node (ref "N5") (pin "12") (pinfunction "0P1V_12") (pintype "passive"))
    )
    (net (code "46") (name "unconnected-(N5-0P8V-Pad9)") (class "Default")
      (node (ref "N5") (pin "9") (pinfunction "0P8V_9") (pintype "passive"))
    )
    (net (code "47") (name "unconnected-(N5-1P6V-Pad8)") (class "Default")
      (node (ref "N5") (pin "8") (pinfunction "1P6V_8") (pintype "passive"))
    )
    (net (code "48") (name "unconnected-(N5-NC-Pad19)") (class "Default")
      (node (ref "N5") (pin "19") (pinfunction "NC_19") (pintype "passive"))
    )
    (net (code "49") (name "unconnected-(N5-NC_2-Pad2)") (class "Default")
      (node (ref "N5") (pin "2") (pinfunction "NC_2_2") (pintype "passive"))
    )
    (net (code "50") (name "unconnected-(N5-NC_3-Pad17)") (class "Default")
      (node (ref "N5") (pin "17") (pinfunction "NC_3_17") (pintype "passive"))
    )
    (net (code "51") (name "unconnected-(N5-NC_4-Pad18)") (class "Default")
      (node (ref "N5") (pin "18") (pinfunction "NC_4_18") (pintype "passive"))
    )
    (net (code "52") (name "unconnected-(U1-NC-Pad19)") (class "Default")
      (node (ref "U1") (pin "19") (pinfunction "NC_19") (pintype "passive"))
    )
    (net (code "53") (name "unconnected-(U1-NC_2-Pad2)") (class "Default")
      (node (ref "U1") (pin "2") (pinfunction "NC_2_2") (pintype "passive"))
    )
    (net (code "54") (name "unconnected-(U1-NC_3-Pad4)") (class "Default")
      (node (ref "U1") (pin "4") (pinfunction "NC_3_4") (pintype "passive"))
    )
    (net (code "55") (name "unconnected-(U1-NC_4-Pad5)") (class "Default")
      (node (ref "U1") (pin "5") (pinfunction "NC_4_5") (pintype "passive"))
    )
    (net (code "56") (name "unconnected-(U1-NC_5-Pad6)") (class "Default")
      (node (ref "U1") (pin "6") (pinfunction "NC_5_6") (pintype "passive"))
    )
    (net (code "57") (name "unconnected-(U1-NC_6-Pad8)") (class "Default")
      (node (ref "U1") (pin "8") (pinfunction "NC_6_8") (pintype "passive"))
    )
    (net (code "58") (name "unconnected-(U1-NC_7-Pad9)") (class "Default")
      (node (ref "U1") (pin "9") (pinfunction "NC_7_9") (pintype "passive"))
    )
    (net (code "59") (name "unconnected-(U1-NC_8-Pad10)") (class "Default")
      (node (ref "U1") (pin "10") (pinfunction "NC_8_10") (pintype "passive"))
    )
    (net (code "60") (name "unconnected-(U1-NC_9-Pad11)") (class "Default")
      (node (ref "U1") (pin "11") (pinfunction "NC_9_11") (pintype "passive"))
    )
    (net (code "61") (name "unconnected-(U1-NC_10-Pad12)") (class "Default")
      (node (ref "U1") (pin "12") (pinfunction "NC_10_12") (pintype "passive"))
    )
    (net (code "62") (name "unconnected-(U1-NC_11-Pad17)") (class "Default")
      (node (ref "U1") (pin "17") (pinfunction "NC_11_17") (pintype "passive"))
    )
    (net (code "63") (name "unconnected-(U1-NC_12-Pad18)") (class "Default")
      (node (ref "U1") (pin "18") (pinfunction "NC_12_18") (pintype "passive"))
    )
  )
)
